# M8_Y-adapter.net
KiCad netlist of a schematic drawn in Altium Designer
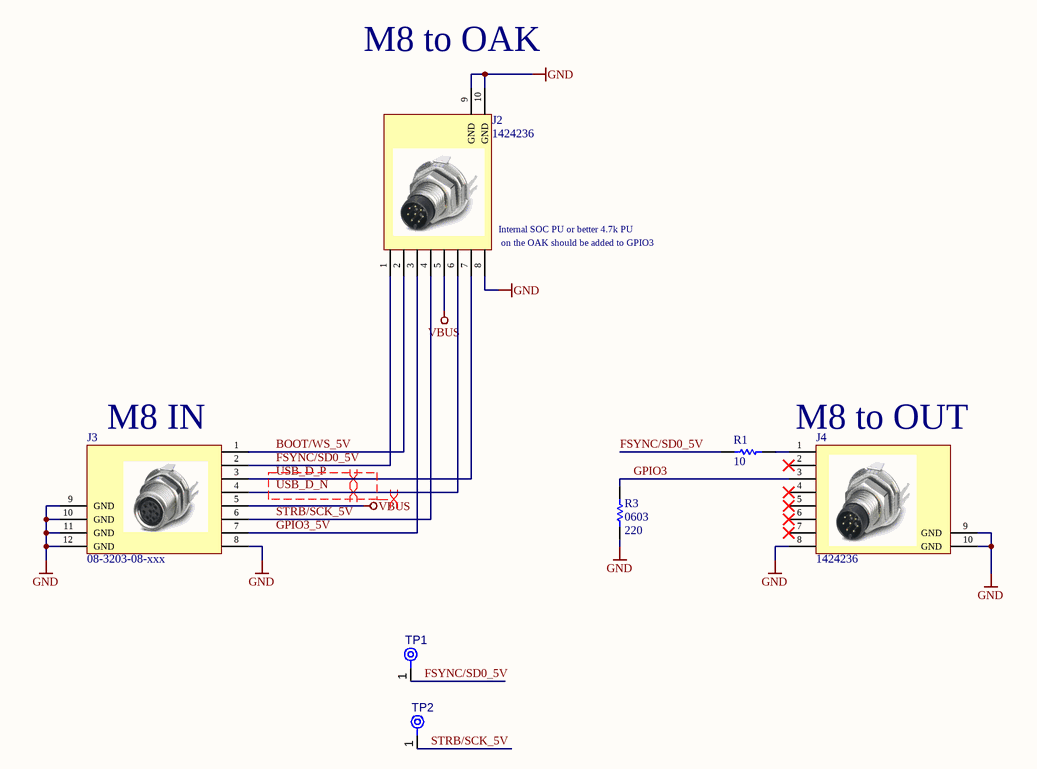
[diagram p0: M8_Y-adapter.SchDoc]

(export (version "E")
  (design (tool "Eeschema 10.0.6"))
  (components
    (comp (ref "J2")
      (value "1424236")
      (footprint "1424236")
      (description "Circular Connector")
      (libsource (lib "") (part "1424236_1"))
    )
    (comp (ref "J3")
      (value "08-3203-08-xxx")
      (footprint "08-3203-08-XXX")
      (description "M8 Circular Connector")
      (libsource (lib "Luxonis LLC") (part "08-3203-08-xxx"))
    )
    (comp (ref "J4")
      (value "1424236")
      (footprint "1424236")
      (description "Circular Connector")
      (libsource (lib "Luxonis LLC") (part "1424236"))
    )
    (comp (ref "R1")
      (value "10")
      (footprint "RESC0603(1608)_N")
      (description "RES SMD 10 OHM 1% 1/10W 0603")
      (fields (field (name "TOLERANCE") "1%") (field (name "Comment") "CRCW060310R0FKEA"))
      (libsource (lib "Luxonis LLC") (part "RC0402FR-0722RL_1"))
    )
    (comp (ref "R3")
      (value "220")
      (footprint "RESC0603(1608)_L")
      (description "RES SMD 220 OHM 1% 0.1W 0603")
      (fields
        (field (name "CASE/PACKAGE") "0603")
        (field (name "TOLERANCE") "1%")
        (field (name "Comment") "RC0603FR-07220RL")
      )
      (libsource (lib "Luxonis LLC") (part "Default resistor symbol"))
    )
    (comp (ref "TP1")
      (value "TPAD6R")
      (footprint "TP06R")
      (description "0.6mm round")
      (libsource (lib "Luxonis LLC") (part "CMP-001-0001-4"))
    )
    (comp (ref "TP2")
      (value "TPAD6R")
      (footprint "TP06R")
      (description "0.6mm round")
      (libsource (lib "Luxonis LLC") (part "CMP-001-0001-4"))
    )
  )
  (nets
    (net (code "1") (name "/BOOT{slash}WS_5V") (class "Default")
      (node (ref "J2") (pin "2") (pinfunction "2_2") (pintype "passive"))
      (node (ref "J3") (pin "1") (pinfunction "1_1") (pintype "passive"))
    )
    (net (code "2") (name "/FSYNC{slash}SD0_5V") (class "Default")
      (node (ref "J2") (pin "1") (pinfunction "1_1") (pintype "passive"))
      (node (ref "J3") (pin "2") (pinfunction "2_2") (pintype "passive"))
      (node (ref "R1") (pin "1") (pinfunction "1_1") (pintype "passive"))
      (node (ref "TP1") (pin "1") (pinfunction "TP_1") (pintype "passive"))
    )
    (net (code "3") (name "/GPIO3") (class "Default")
      (node (ref "J4") (pin "3") (pinfunction "3_3") (pintype "passive"))
      (node (ref "R3") (pin "2") (pinfunction "2_2") (pintype "passive"))
    )
    (net (code "4") (name "/GPIO3_5V") (class "Default")
      (node (ref "J2") (pin "3") (pinfunction "3_3") (pintype "passive"))
      (node (ref "J3") (pin "7") (pinfunction "7_7") (pintype "passive"))
    )
    (net (code "5") (name "/STRB{slash}SCK_5V") (class "Default")
      (node (ref "J2") (pin "4") (pinfunction "4_4") (pintype "passive"))
      (node (ref "J3") (pin "6") (pinfunction "6_6") (pintype "passive"))
      (node (ref "TP2") (pin "1") (pinfunction "TP_1") (pintype "passive"))
    )
    (net (code "6") (name "/USB_D_N") (class "Default")
      (node (ref "J2") (pin "6") (pinfunction "6_6") (pintype "passive"))
      (node (ref "J3") (pin "4") (pinfunction "4_4") (pintype "passive"))
    )
    (net (code "7") (name "/USB_D_P") (class "Default")
      (node (ref "J2") (pin "7") (pinfunction "7_7") (pintype "passive"))
      (node (ref "J3") (pin "3") (pinfunction "3_3") (pintype "passive"))
    )
    (net (code "8") (name "GND") (class "Default")
      (node (ref "J2") (pin "10") (pinfunction "GND_10") (pintype "passive"))
      (node (ref "J2") (pin "8") (pinfunction "8_8") (pintype "passive"))
      (node (ref "J2") (pin "9") (pinfunction "GND_9") (pintype "passive"))
      (node (ref "J3") (pin "10") (pinfunction "GND_10") (pintype "passive"))
      (node (ref "J3") (pin "11") (pinfunction "GND_11") (pintype "passive"))
      (node (ref "J3") (pin "12") (pinfunction "GND_12") (pintype "passive"))
      (node (ref "J3") (pin "8") (pinfunction "8_8") (pintype "passive"))
      (node (ref "J3") (pin "9") (pinfunction "GND_9") (pintype "passive"))
      (node (ref "J4") (pin "10") (pinfunction "GND_10") (pintype "passive"))
      (node (ref "J4") (pin "8") (pinfunction "8_8") (pintype "passive"))
      (node (ref "J4") (pin "9") (pinfunction "GND_9") (pintype "passive"))
      (node (ref "R3") (pin "1") (pinfunction "1_1") (pintype "passive"))
    )
    (net (code "9") (name "Net-(J4-Pad1)") (class "Default")
      (node (ref "J4") (pin "1") (pinfunction "1_1") (pintype "passive"))
      (node (ref "R1") (pin "2") (pinfunction "2_2") (pintype "passive"))
    )
    (net (code "10") (name "VBUS") (class "Default")
      (node (ref "J2") (pin "5") (pinfunction "5_5") (pintype "passive"))
      (node (ref "J3") (pin "5") (pinfunction "5_5") (pintype "passive"))
    )
    (net (code "11") (name "unconnected-(J4-Pad2)") (class "Default")
      (node (ref "J4") (pin "2") (pinfunction "2_2") (pintype "passive+no_connect"))
    )
    (net (code "12") (name "unconnected-(J4-Pad4)") (class "Default")
      (node (ref "J4") (pin "4") (pinfunction "4_4") (pintype "passive+no_connect"))
    )
    (net (code "13") (name "unconnected-(J4-Pad5)") (class "Default")
      (node (ref "J4") (pin "5") (pinfunction "5_5") (pintype "passive+no_connect"))
    )
    (net (code "14") (name "unconnected-(J4-Pad6)") (class "Default")
      (node (ref "J4") (pin "6") (pinfunction "6_6") (pintype "passive+no_connect"))
    )
    (net (code "15") (name "unconnected-(J4-Pad7)") (class "Default")
      (node (ref "J4") (pin "7") (pinfunction "7_7") (pintype "passive+no_connect"))
    )
  )
)
